# PIC32MK.net
KiCad netlist of a schematic drawn in Altium Designer
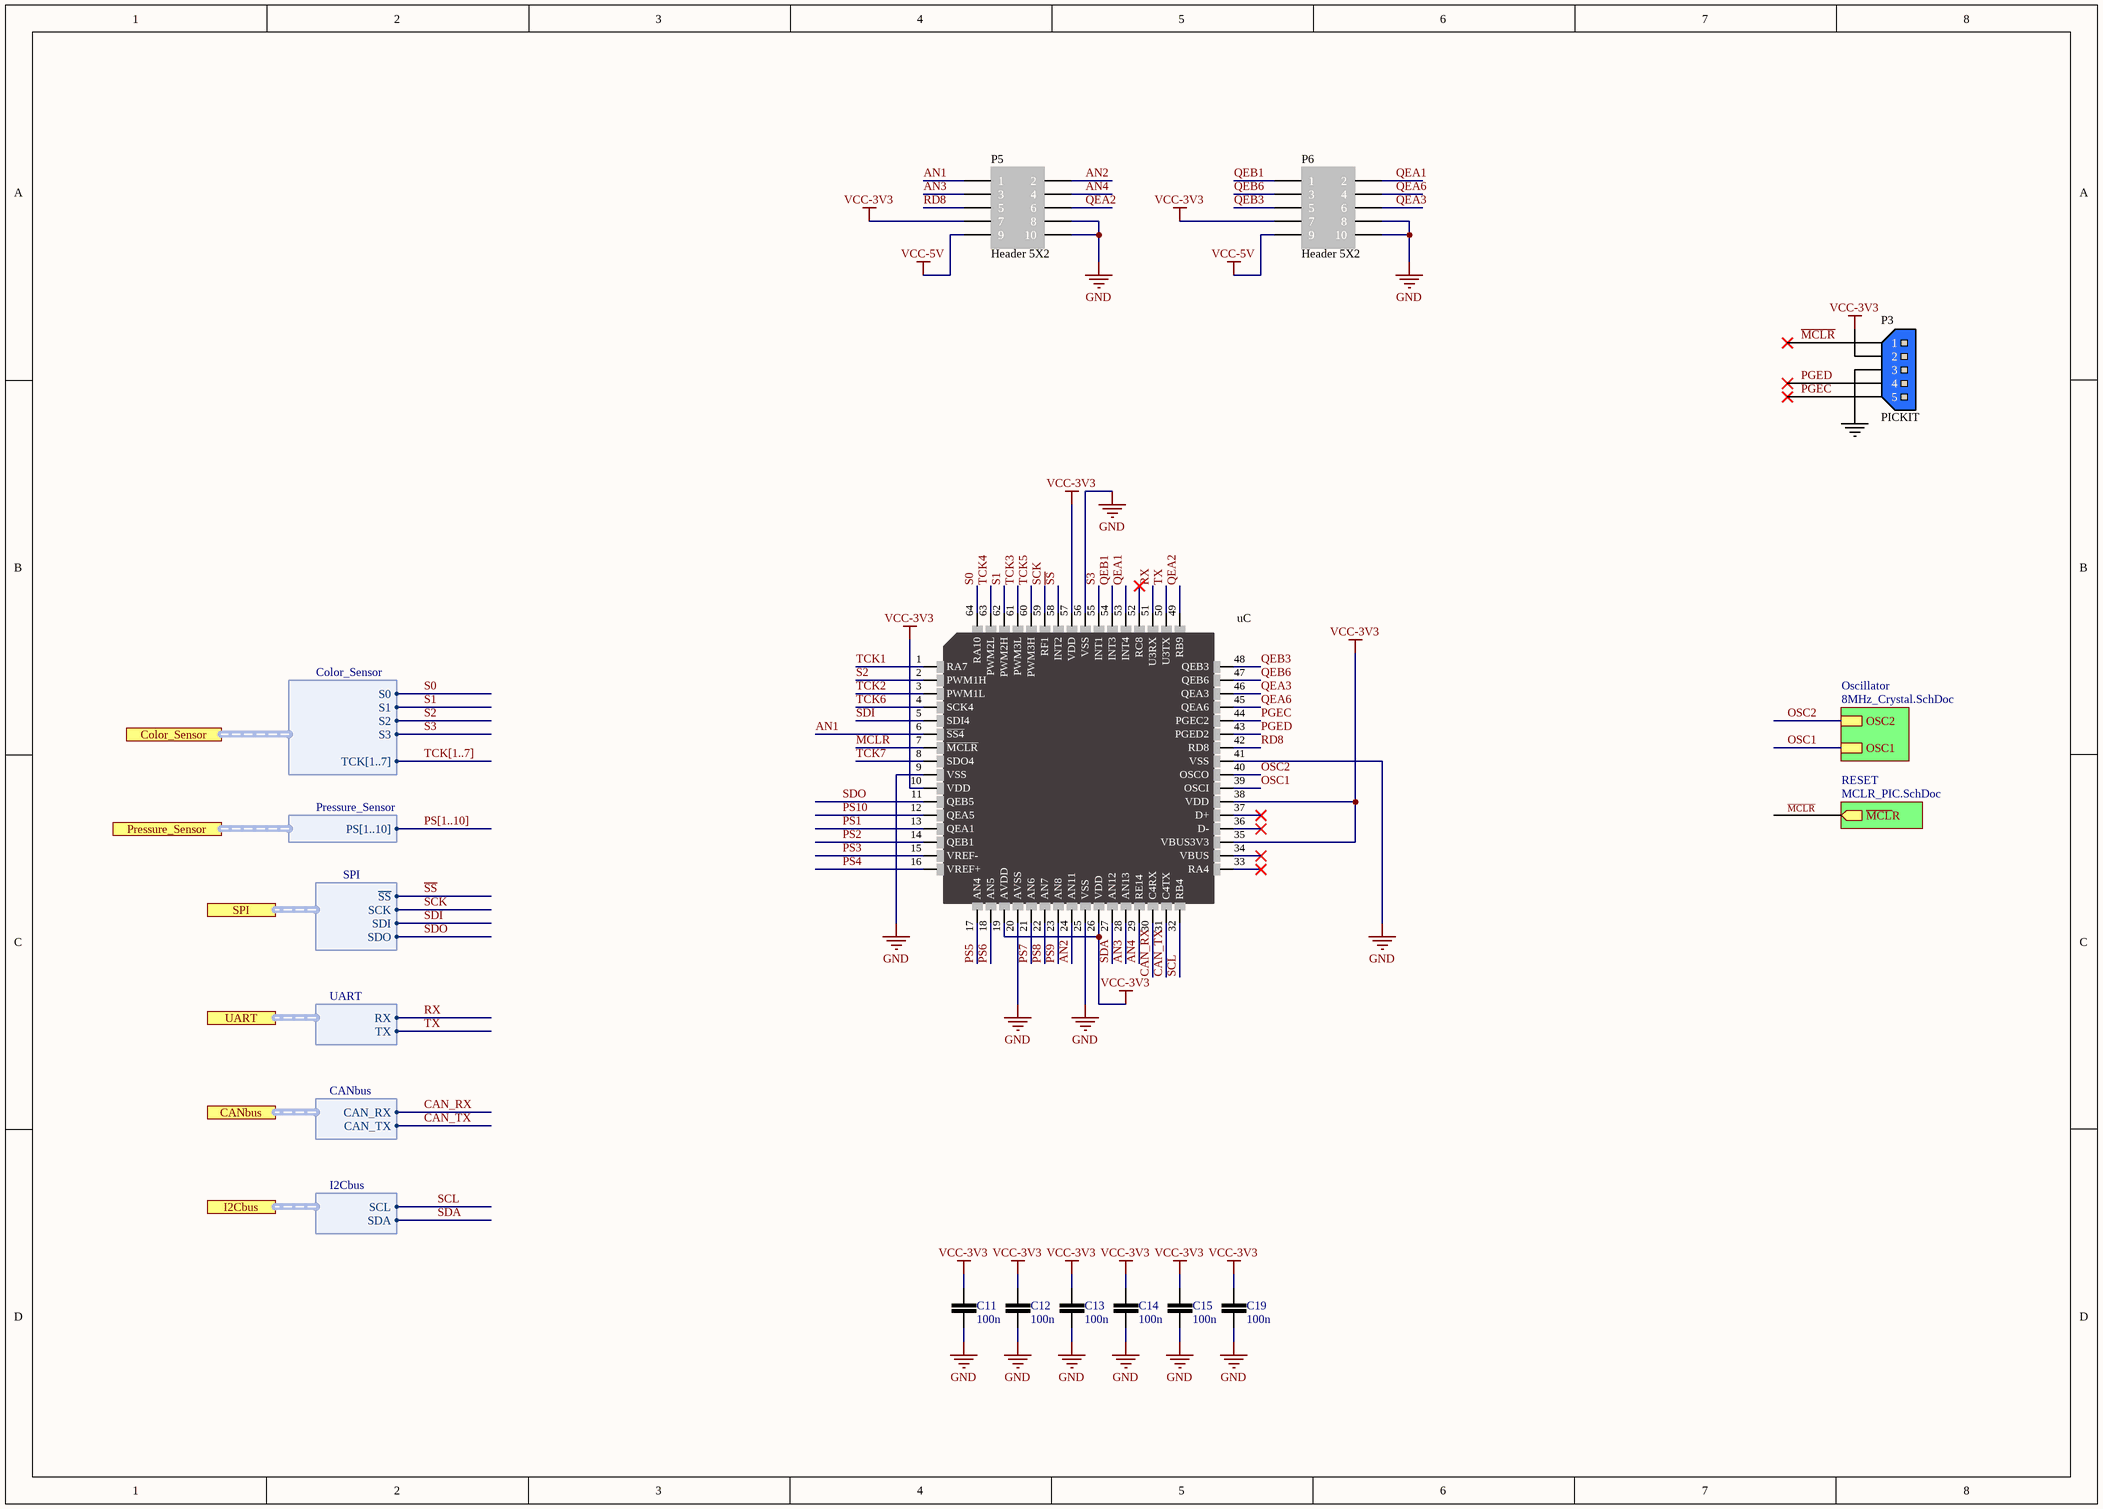
[diagram p0: PIC32MK.SchDoc]

(export (version "E")
  (design (tool "Eeschema 10.0.6"))
  (components
    (comp (ref "C11")
      (value "100n")
      (footprint "CER_0805")
      (fields
        (field (name "MANUFACTURER") "Yageo")
        (field (name "MANUFACTURER PART NUMBER") "CC0805KRX7R9BB104")
        (field (name "TOLERANCE") "10%")
      )
      (libsource (lib "capacitors") (part "0100000001868"))
    )
    (comp (ref "C12")
      (value "100n")
      (footprint "CER_0805")
      (fields
        (field (name "MANUFACTURER") "Yageo")
        (field (name "MANUFACTURER PART NUMBER") "CC0805KRX7R9BB104")
        (field (name "TOLERANCE") "10%")
      )
      (libsource (lib "capacitors") (part "0100000001868"))
    )
    (comp (ref "C13")
      (value "100n")
      (footprint "CER_0805")
      (fields
        (field (name "MANUFACTURER") "Yageo")
        (field (name "MANUFACTURER PART NUMBER") "CC0805KRX7R9BB104")
        (field (name "TOLERANCE") "10%")
      )
      (libsource (lib "capacitors") (part "0100000001868"))
    )
    (comp (ref "C14")
      (value "100n")
      (footprint "CER_0805")
      (fields
        (field (name "MANUFACTURER") "Yageo")
        (field (name "MANUFACTURER PART NUMBER") "CC0805KRX7R9BB104")
        (field (name "TOLERANCE") "10%")
      )
      (libsource (lib "capacitors") (part "0100000001868"))
    )
    (comp (ref "C15")
      (value "100n")
      (footprint "CER_0805")
      (fields
        (field (name "MANUFACTURER") "Yageo")
        (field (name "MANUFACTURER PART NUMBER") "CC0805KRX7R9BB104")
        (field (name "TOLERANCE") "10%")
      )
      (libsource (lib "capacitors") (part "0100000001868"))
    )
    (comp (ref "C19")
      (value "100n")
      (footprint "CER_0805")
      (fields
        (field (name "MANUFACTURER") "Yageo")
        (field (name "MANUFACTURER PART NUMBER") "CC0805KRX7R9BB104")
        (field (name "TOLERANCE") "10%")
      )
      (libsource (lib "capacitors") (part "0100000001868"))
    )
    (comp (ref "P3")
      (value "PICKIT")
      (footprint "TE CONNECTIVITY_5PIN_MALE")
      (description "BLUE_5PIN_CONECTOR")
      (fields (field (name "MANUFACTURER") "TE CONNECTIVITY / AMP"))
      (libsource (lib "Electro_Mechanical") (part "TE CONNECTIVITY_5PIN_MALE"))
    )
    (comp (ref "P5")
      (value "Header 5X2")
      (footprint "CONNECTOR_2X5")
      (description "Header, 5-Pin, Dual row")
      (fields (field (name "PUBLISHER") "Altium Limited"))
      (libsource (lib "Electro_Mechanical") (part "Header 5X2"))
    )
    (comp (ref "P6")
      (value "Header 5X2")
      (footprint "CONNECTOR_2X5")
      (description "Header, 5-Pin, Dual row")
      (fields (field (name "PUBLISHER") "Altium Limited"))
      (libsource (lib "Electro_Mechanical") (part "Header 5X2"))
    )
    (comp (ref "uC")
      (value "~")
      (footprint "TQFP-64-500um")
      (description "IC MCU 32BIT 1MB FLASH 64TQFP")
      (fields (field (name "MANUFACTURER PART NUMBER") "PIC32MK1024MCF064"))
      (libsource (lib "Integrated_circuits") (part "PIC32MK1024MCF064"))
    )
  )
  (nets
    (net (code "7") (name "/AN1") (class "Default")
      (node (ref "P5") (pin "1") (pinfunction "1_1") (pintype "passive"))
      (node (ref "uC") (pin "6") (pinfunction "~{SS4}_6") (pintype "passive"))
    )
    (net (code "8") (name "/AN2") (class "Default")
      (node (ref "P5") (pin "2") (pinfunction "2_2") (pintype "passive"))
      (node (ref "uC") (pin "24") (pinfunction "AN11_24") (pintype "passive"))
    )
    (net (code "9") (name "/AN3") (class "Default")
      (node (ref "P5") (pin "3") (pinfunction "3_3") (pintype "passive"))
      (node (ref "uC") (pin "28") (pinfunction "AN13_28") (pintype "passive"))
    )
    (net (code "10") (name "/AN4") (class "Default")
      (node (ref "P5") (pin "4") (pinfunction "4_4") (pintype "passive"))
      (node (ref "uC") (pin "29") (pinfunction "RE14_29") (pintype "passive"))
    )
    (net (code "11") (name "/CAN_RX") (class "Default")
      (node (ref "uC") (pin "30") (pinfunction "C4RX_30") (pintype "passive"))
    )
    (net (code "12") (name "/CAN_TX") (class "Default")
      (node (ref "uC") (pin "31") (pinfunction "C4TX_31") (pintype "passive"))
    )
    (net (code "13") (name "/OSC1") (class "Default")
      (node (ref "uC") (pin "39") (pinfunction "OSCI_39") (pintype "passive"))
    )
    (net (code "14") (name "/OSC2") (class "Default")
      (node (ref "uC") (pin "40") (pinfunction "OSCO_40") (pintype "passive"))
    )
    (net (code "15") (name "/PGEC") (class "Default")
      (node (ref "P3") (pin "5") (pinfunction "5_5") (pintype "passive"))
      (node (ref "uC") (pin "44") (pinfunction "PGEC2_44") (pintype "passive"))
    )
    (net (code "16") (name "/PGED") (class "Default")
      (node (ref "P3") (pin "4") (pinfunction "4_4") (pintype "passive"))
      (node (ref "uC") (pin "43") (pinfunction "PGED2_43") (pintype "passive"))
    )
    (net (code "17") (name "/PS1") (class "Default")
      (node (ref "uC") (pin "13") (pinfunction "QEA1_13") (pintype "passive"))
    )
    (net (code "18") (name "/PS2") (class "Default")
      (node (ref "uC") (pin "14") (pinfunction "QEB1_14") (pintype "passive"))
    )
    (net (code "19") (name "/PS3") (class "Default")
      (node (ref "uC") (pin "15") (pinfunction "VREF-_15") (pintype "passive"))
    )
    (net (code "20") (name "/PS4") (class "Default")
      (node (ref "uC") (pin "16") (pinfunction "VREF+_16") (pintype "passive"))
    )
    (net (code "21") (name "/PS5") (class "Default")
      (node (ref "uC") (pin "17") (pinfunction "AN4_17") (pintype "passive"))
    )
    (net (code "22") (name "/PS6") (class "Default")
      (node (ref "uC") (pin "18") (pinfunction "AN5_18") (pintype "passive"))
    )
    (net (code "23") (name "/PS7") (class "Default")
      (node (ref "uC") (pin "21") (pinfunction "AN6_21") (pintype "passive"))
    )
    (net (code "24") (name "/PS8") (class "Default")
      (node (ref "uC") (pin "22") (pinfunction "AN7_22") (pintype "passive"))
    )
    (net (code "25") (name "/PS9") (class "Default")
      (node (ref "uC") (pin "23") (pinfunction "AN8_23") (pintype "passive"))
    )
    (net (code "26") (name "/PS10") (class "Default")
      (node (ref "uC") (pin "12") (pinfunction "QEA5_12") (pintype "passive"))
    )
    (net (code "28") (name "/QEA1") (class "Default")
      (node (ref "P6") (pin "2") (pinfunction "2_2") (pintype "passive"))
      (node (ref "uC") (pin "53") (pinfunction "INT4_53") (pintype "passive"))
    )
    (net (code "29") (name "/QEA2") (class "Default")
      (node (ref "P5") (pin "6") (pinfunction "6_6") (pintype "passive"))
      (node (ref "uC") (pin "49") (pinfunction "RB9_49") (pintype "passive"))
    )
    (net (code "30") (name "/QEA3") (class "Default")
      (node (ref "P6") (pin "6") (pinfunction "6_6") (pintype "passive"))
      (node (ref "uC") (pin "46") (pinfunction "QEA3_46") (pintype "passive"))
    )
    (net (code "31") (name "/QEA6") (class "Default")
      (node (ref "P6") (pin "4") (pinfunction "4_4") (pintype "passive"))
      (node (ref "uC") (pin "45") (pinfunction "QEA6_45") (pintype "passive"))
    )
    (net (code "32") (name "/QEB1") (class "Default")
      (node (ref "P6") (pin "1") (pinfunction "1_1") (pintype "passive"))
      (node (ref "uC") (pin "54") (pinfunction "INT3_54") (pintype "passive"))
    )
    (net (code "33") (name "/QEB3") (class "Default")
      (node (ref "P6") (pin "5") (pinfunction "5_5") (pintype "passive"))
      (node (ref "uC") (pin "48") (pinfunction "QEB3_48") (pintype "passive"))
    )
    (net (code "34") (name "/QEB6") (class "Default")
      (node (ref "P6") (pin "3") (pinfunction "3_3") (pintype "passive"))
      (node (ref "uC") (pin "47") (pinfunction "QEB6_47") (pintype "passive"))
    )
    (net (code "35") (name "/RD8") (class "Default")
      (node (ref "P5") (pin "5") (pinfunction "5_5") (pintype "passive"))
      (node (ref "uC") (pin "42") (pinfunction "RD8_42") (pintype "passive"))
    )
    (net (code "36") (name "/RX") (class "Default")
      (node (ref "uC") (pin "51") (pinfunction "U3RX_51") (pintype "passive"))
    )
    (net (code "37") (name "/S0") (class "Default")
      (node (ref "uC") (pin "64") (pinfunction "RA10_64") (pintype "passive"))
    )
    (net (code "38") (name "/S1") (class "Default")
      (node (ref "uC") (pin "62") (pinfunction "PWM2H_62") (pintype "passive"))
    )
    (net (code "39") (name "/S2") (class "Default")
      (node (ref "uC") (pin "2") (pinfunction "PWM1H_2") (pintype "passive"))
    )
    (net (code "40") (name "/S3") (class "Default")
      (node (ref "uC") (pin "55") (pinfunction "INT1_55") (pintype "passive"))
    )
    (net (code "41") (name "/SCK") (class "Default")
      (node (ref "uC") (pin "59") (pinfunction "RF1_59") (pintype "passive"))
    )
    (net (code "42") (name "/SCL") (class "Default")
      (node (ref "uC") (pin "32") (pinfunction "RB4_32") (pintype "passive"))
    )
    (net (code "43") (name "/SDA") (class "Default")
      (node (ref "uC") (pin "27") (pinfunction "AN12_27") (pintype "passive"))
    )
    (net (code "44") (name "/SDI") (class "Default")
      (node (ref "uC") (pin "5") (pinfunction "SDI4_5") (pintype "passive"))
    )
    (net (code "45") (name "/SDO") (class "Default")
      (node (ref "uC") (pin "11") (pinfunction "QEB5_11") (pintype "passive"))
    )
    (net (code "46") (name "/TCK1") (class "Default")
      (node (ref "uC") (pin "1") (pinfunction "RA7_1") (pintype "passive"))
    )
    (net (code "47") (name "/TCK2") (class "Default")
      (node (ref "uC") (pin "3") (pinfunction "PWM1L_3") (pintype "passive"))
    )
    (net (code "48") (name "/TCK3") (class "Default")
      (node (ref "uC") (pin "61") (pinfunction "PWM3L_61") (pintype "passive"))
    )
    (net (code "49") (name "/TCK4") (class "Default")
      (node (ref "uC") (pin "63") (pinfunction "PWM2L_63") (pintype "passive"))
    )
    (net (code "50") (name "/TCK5") (class "Default")
      (node (ref "uC") (pin "60") (pinfunction "PWM3H_60") (pintype "passive"))
    )
    (net (code "51") (name "/TCK6") (class "Default")
      (node (ref "uC") (pin "4") (pinfunction "SCK4_4") (pintype "passive"))
    )
    (net (code "52") (name "/TCK7") (class "Default")
      (node (ref "uC") (pin "8") (pinfunction "SDO4_8") (pintype "passive"))
    )
    (net (code "54") (name "/TX") (class "Default")
      (node (ref "uC") (pin "50") (pinfunction "U3TX_50") (pintype "passive"))
    )
    (net (code "61") (name "/~{MCLR}") (class "Default")
      (node (ref "P3") (pin "1") (pinfunction "1_1") (pintype "passive"))
      (node (ref "uC") (pin "7") (pinfunction "~{MCLR}_7") (pintype "passive"))
    )
    (net (code "62") (name "/~{SS}") (class "Default")
      (node (ref "uC") (pin "58") (pinfunction "INT2_58") (pintype "passive"))
    )
    (net (code "63") (name "GND") (class "Default")
      (node (ref "C11") (pin "1") (pinfunction "1_1") (pintype "passive"))
      (node (ref "C12") (pin "1") (pinfunction "1_1") (pintype "passive"))
      (node (ref "C13") (pin "1") (pinfunction "1_1") (pintype "passive"))
      (node (ref "C14") (pin "1") (pinfunction "1_1") (pintype "passive"))
      (node (ref "C15") (pin "1") (pinfunction "1_1") (pintype "passive"))
      (node (ref "C19") (pin "1") (pinfunction "1_1") (pintype "passive"))
      (node (ref "P3") (pin "3") (pinfunction "3_3") (pintype "passive"))
      (node (ref "P5") (pin "10") (pinfunction "10_10") (pintype "passive"))
      (node (ref "P5") (pin "8") (pinfunction "8_8") (pintype "passive"))
      (node (ref "P6") (pin "10") (pinfunction "10_10") (pintype "passive"))
      (node (ref "P6") (pin "8") (pinfunction "8_8") (pintype "passive"))
      (node (ref "uC") (pin "20") (pinfunction "AVSS_20") (pintype "passive"))
      (node (ref "uC") (pin "25") (pinfunction "VSS_25") (pintype "passive"))
      (node (ref "uC") (pin "41") (pinfunction "VSS_41") (pintype "passive"))
      (node (ref "uC") (pin "56") (pinfunction "VSS_56") (pintype "passive"))
      (node (ref "uC") (pin "9") (pinfunction "VSS_9") (pintype "passive"))
    )
    (net (code "64") (name "VCC-3V3") (class "Default")
      (node (ref "C11") (pin "2") (pinfunction "2_2") (pintype "passive"))
      (node (ref "C12") (pin "2") (pinfunction "2_2") (pintype "passive"))
      (node (ref "C13") (pin "2") (pinfunction "2_2") (pintype "passive"))
      (node (ref "C14") (pin "2") (pinfunction "2_2") (pintype "passive"))
      (node (ref "C15") (pin "2") (pinfunction "2_2") (pintype "passive"))
      (node (ref "C19") (pin "2") (pinfunction "2_2") (pintype "passive"))
      (node (ref "P3") (pin "2") (pinfunction "2_2") (pintype "passive"))
      (node (ref "P5") (pin "7") (pinfunction "7_7") (pintype "passive"))
      (node (ref "P6") (pin "7") (pinfunction "7_7") (pintype "passive"))
      (node (ref "uC") (pin "10") (pinfunction "VDD_10") (pintype "passive"))
      (node (ref "uC") (pin "19") (pinfunction "AVDD_19") (pintype "passive"))
      (node (ref "uC") (pin "26") (pinfunction "VDD_26") (pintype "passive"))
      (node (ref "uC") (pin "35") (pinfunction "VBUS3V3_35") (pintype "passive"))
      (node (ref "uC") (pin "38") (pinfunction "VDD_38") (pintype "passive"))
      (node (ref "uC") (pin "57") (pinfunction "VDD_57") (pintype "passive"))
    )
    (net (code "65") (name "VCC-5V") (class "Default")
      (node (ref "P5") (pin "9") (pinfunction "9_9") (pintype "passive"))
      (node (ref "P6") (pin "9") (pinfunction "9_9") (pintype "passive"))
    )
    (net (code "66") (name "unconnected-(uC-D+-Pad37)") (class "Default")
      (node (ref "uC") (pin "37") (pinfunction "D+_37") (pintype "passive+no_connect"))
    )
    (net (code "67") (name "unconnected-(uC-D--Pad36)") (class "Default")
      (node (ref "uC") (pin "36") (pinfunction "D-_36") (pintype "passive+no_connect"))
    )
    (net (code "68") (name "unconnected-(uC-RA4-Pad33)") (class "Default")
      (node (ref "uC") (pin "33") (pinfunction "RA4_33") (pintype "passive+no_connect"))
    )
    (net (code "69") (name "unconnected-(uC-RC8-Pad52)") (class "Default")
      (node (ref "uC") (pin "52") (pinfunction "RC8_52") (pintype "passive+no_connect"))
    )
    (net (code "70") (name "unconnected-(uC-VBUS-Pad34)") (class "Default")
      (node (ref "uC") (pin "34") (pinfunction "VBUS_34") (pintype "passive+no_connect"))
    )
  )
)
